# Sheet1.net
KiCad netlist of a schematic drawn in Altium Designer
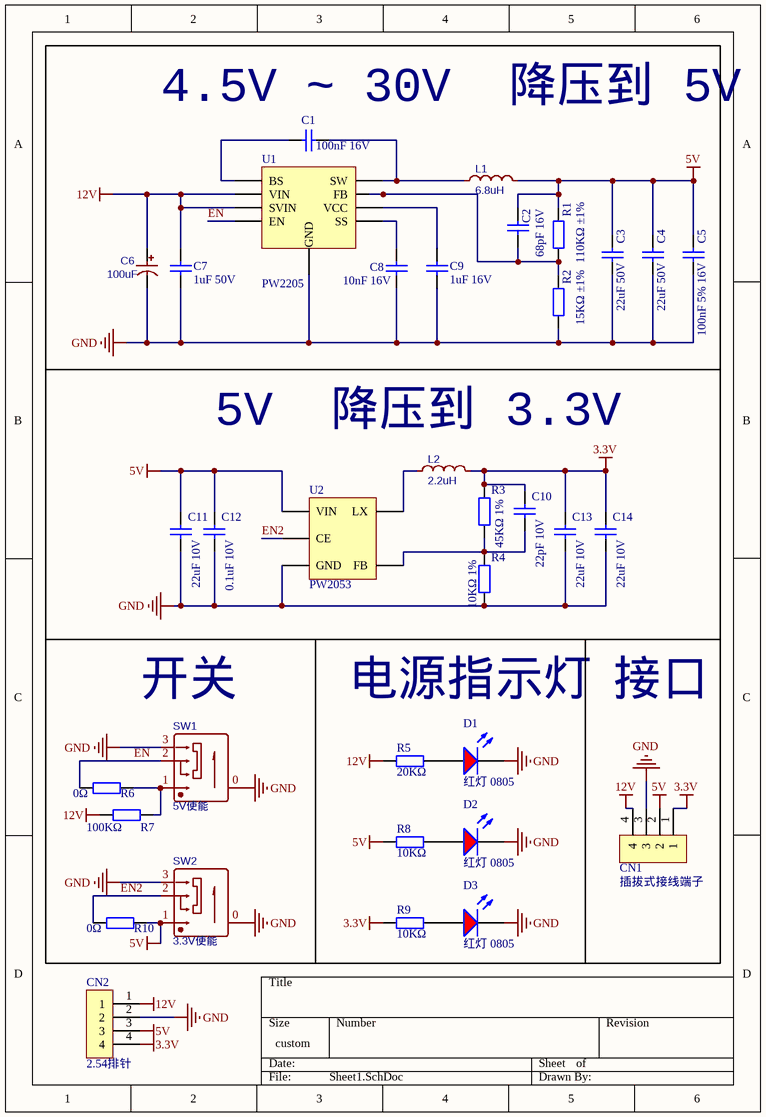
[diagram p0: Sheet1.SchDoc]

(export (version "E")
  (design (tool "Eeschema 10.0.6"))
  (components
    (comp (ref "C1")
      (value "100nF 16V")
      (footprint "0805_C")
      (description "贴片电容")
      (libsource (lib "Miscellaneous Devices LC") (part "0805 100nF(104) 10% 50V"))
    )
    (comp (ref "C2")
      (value "68pF 16V")
      (footprint "0805_C")
      (description "贴片电容")
      (libsource (lib "Miscellaneous Devices LC") (part "0805 68pF (680) 5% 50V"))
    )
    (comp (ref "C3")
      (value "22uF 50V")
      (footprint "0805_C")
      (description "贴片电容")
      (libsource (lib "Miscellaneous Devices LC") (part "0805 22uF (226) 20% 25V"))
    )
    (comp (ref "C4")
      (value "22uF 50V")
      (footprint "0805_C")
      (description "贴片电容")
      (libsource (lib "Miscellaneous Devices LC") (part "0805 22uF (226) 20% 25V"))
    )
    (comp (ref "C5")
      (value "100nF 5% 16V")
      (footprint "0805_C")
      (description "贴片电容")
      (libsource (lib "Miscellaneous Devices LC") (part "0805 100nF(104) 10% 50V"))
    )
    (comp (ref "C6")
      (value "100uF")
      (footprint "电容 6.3*8")
      (fields
        (field (name "BOM_MANUFACTURER PART") "SPZ1VM101E08000R")
        (field (name "BOM_SUPPLIER PART") "C122240")
      )
      (libsource (lib "BalanceCar") (part "电容 6.3*8"))
    )
    (comp (ref "C7")
      (value "1uF 50V")
      (footprint "0805_C")
      (description "贴片电容")
      (libsource (lib "Miscellaneous Devices LC") (part "0805 1uF (105) 10% 50V"))
    )
    (comp (ref "C8")
      (value "10nF 16V")
      (footprint "0805_C")
      (description "贴片电容")
      (libsource (lib "Miscellaneous Devices LC") (part "0805 10nF (103) 10% 50V"))
    )
    (comp (ref "C9")
      (value "1uF 16V")
      (footprint "0805_C")
      (description "贴片电容")
      (libsource (lib "Miscellaneous Devices LC") (part "0805 1uF (105) 10% 50V"))
    )
    (comp (ref "C10")
      (value "22pF 10V")
      (footprint "0805_C")
      (description "贴片电容")
      (libsource (lib "Miscellaneous Devices LC") (part "0603 10pF (100) 5% 50V"))
    )
    (comp (ref "C11")
      (value "22uF 10V")
      (footprint "0805_C")
      (description "贴片电容")
      (libsource (lib "Miscellaneous Devices LC") (part "0805 22uF (226) 20% 25V"))
    )
    (comp (ref "C12")
      (value "0.1uF 10V")
      (footprint "0805_C")
      (description "贴片电容")
      (libsource (lib "Miscellaneous Devices LC") (part "0603 10pF (100) 5% 50V"))
    )
    (comp (ref "C13")
      (value "22uF 10V")
      (footprint "0805_C")
      (description "贴片电容")
      (libsource (lib "Miscellaneous Devices LC") (part "0805 22uF (226) 20% 25V"))
    )
    (comp (ref "C14")
      (value "22uF 10V")
      (footprint "0805_C")
      (description "贴片电容")
      (libsource (lib "Miscellaneous Devices LC") (part "0805 22uF (226) 20% 25V"))
    )
    (comp (ref "CN1")
      (value "插拔式接线端子")
      (footprint "插拔式接线端子-弯插")
      (libsource (lib "DCDC_Power") (part "插拔式接线端子"))
    )
    (comp (ref "CN2") (value "2.54排针") (footprint "2.54排针") (libsource (lib "DCDC_Power") (part "2.54排针")))
    (comp (ref "D1")
      (value "红灯 0805")
      (footprint "0805_LED_S1")
      (description "发光二极管")
      (libsource (lib "Miscellaneous Devices LC") (part "0805 红灯"))
    )
    (comp (ref "D2")
      (value "红灯 0805")
      (footprint "0805_LED_S1")
      (description "发光二极管")
      (libsource (lib "Miscellaneous Devices LC") (part "0805 红灯"))
    )
    (comp (ref "D3")
      (value "红灯 0805")
      (footprint "0805_LED_S1")
      (description "发光二极管")
      (libsource (lib "Miscellaneous Devices LC") (part "0805 红灯"))
    )
    (comp (ref "L1")
      (value "6.8uH")
      (footprint "电感 0650")
      (fields
        (field (name "BOM_SUPPLIER PART") "C475530")
        (field (name "BOM_MANUFACTURER PART") "FXL0650-6R8-M")
        (field (name "CONTRIBUTOR") "LCSC")
      )
      (libsource (lib "BalanceCar") (part "电感 6.8uH"))
    )
    (comp (ref "L2")
      (value "2.2uH")
      (footprint "电感 0520")
      (fields
        (field (name "BOM_SUPPLIER PART") "C475530")
        (field (name "BOM_MANUFACTURER PART") "FXL0650-6R8-M")
        (field (name "CONTRIBUTOR") "LCSC")
      )
      (libsource (lib "") (part "电感 6.8uH_1"))
    )
    (comp (ref "R1")
      (value "110KΩ ±1%")
      (footprint "0805_R")
      (description "贴片电阻")
      (libsource (lib "Miscellaneous Devices LC") (part "0805 110KΩ (1103) 1%"))
    )
    (comp (ref "R2")
      (value "15KΩ ±1%")
      (footprint "0805_R")
      (description "贴片电阻")
      (libsource (lib "Miscellaneous Devices LC") (part "0805 15KΩ (1502) 1%"))
    )
    (comp (ref "R3")
      (value "45KΩ 1%")
      (footprint "0805_R")
      (description "贴片电阻")
      (libsource (lib "Miscellaneous Devices LC") (part "0603 10KΩ (1002) 1%"))
    )
    (comp (ref "R4")
      (value "10KΩ 1%")
      (footprint "0805_R")
      (description "贴片电阻")
      (libsource (lib "Miscellaneous Devices LC") (part "0603 10KΩ (1002) 1%"))
    )
    (comp (ref "R5")
      (value "20KΩ")
      (footprint "0805_R")
      (description "贴片电阻")
      (libsource (lib "Miscellaneous Devices LC") (part "0805 4.7KΩ (4701) 1%"))
    )
    (comp (ref "R6")
      (value "0Ω")
      (footprint "0805_R")
      (description "贴片电阻")
      (libsource (lib "Miscellaneous Devices LC") (part "0805 0Ω (0R0) 1%"))
    )
    (comp (ref "R7")
      (value "100KΩ")
      (footprint "0805_R")
      (description "贴片电阻")
      (libsource (lib "Miscellaneous Devices LC") (part "0805 100KΩ (1003) 1%"))
    )
    (comp (ref "R8")
      (value "10KΩ")
      (footprint "0805_R")
      (description "贴片电阻")
      (libsource (lib "Miscellaneous Devices LC") (part "0805 1KΩ (1001) 1%"))
    )
    (comp (ref "R9")
      (value "10KΩ")
      (footprint "0805_R")
      (description "贴片电阻")
      (libsource (lib "Miscellaneous Devices LC") (part "0805 1KΩ (1001) 1%"))
    )
    (comp (ref "R10")
      (value "0Ω")
      (footprint "0805_R")
      (description "贴片电阻")
      (libsource (lib "Miscellaneous Devices LC") (part "0805 0Ω (0R0) 1%"))
    )
    (comp (ref "SW1")
      (value "5V使能")
      (footprint "拨动开关(侧)")
      (fields
        (field (name "BOM_SUPPLIER PART") "C319020")
        (field (name "BOM_MANUFACTURER PART") "SK-3296S-01-L1")
        (field (name "CONTRIBUTOR") "LCSC")
      )
      (libsource (lib "DCDC_Power") (part "拨动开关(侧)"))
    )
    (comp (ref "SW2")
      (value "3.3V使能")
      (footprint "拨动开关(侧)")
      (fields
        (field (name "BOM_SUPPLIER PART") "C319020")
        (field (name "BOM_MANUFACTURER PART") "SK-3296S-01-L1")
        (field (name "CONTRIBUTOR") "LCSC")
      )
      (libsource (lib "DCDC_Power") (part "拨动开关(侧)"))
    )
    (comp (ref "U1")
      (value "PW2205")
      (footprint "PW2205 - SOP8")
      (libsource (lib "BalanceCar") (part "PW2205"))
    )
    (comp (ref "U2")
      (value "PW2053")
      (footprint "PW2053 - SOT23-6")
      (libsource (lib "BalanceCar") (part "PW2053"))
    )
  )
  (nets
    (net (code "1") (name "/EN") (class "Default")
      (node (ref "R6") (pin "1") (pinfunction "1_1") (pintype "passive"))
      (node (ref "SW1") (pin "2") (pinfunction "2_2") (pintype "passive"))
      (node (ref "U1") (pin "EN") (pinfunction "EN_EN") (pintype "passive"))
    )
    (net (code "2") (name "/EN2") (class "Default")
      (node (ref "R10") (pin "1") (pinfunction "1_1") (pintype "passive"))
      (node (ref "SW2") (pin "2") (pinfunction "2_2") (pintype "passive"))
      (node (ref "U2") (pin "CE") (pinfunction "CE_CE") (pintype "passive"))
    )
    (net (code "3") (name "3.3V") (class "Default")
      (node (ref "C10") (pin "2") (pinfunction "2_2") (pintype "passive"))
      (node (ref "C13") (pin "2") (pinfunction "2_2") (pintype "passive"))
      (node (ref "C14") (pin "2") (pinfunction "2_2") (pintype "passive"))
      (node (ref "CN1") (pin "1") (pinfunction "1_1") (pintype "passive"))
      (node (ref "CN2") (pin "4") (pinfunction "4_4") (pintype "passive"))
      (node (ref "L2") (pin "2") (pinfunction "2_2") (pintype "passive"))
      (node (ref "R3") (pin "2") (pinfunction "2_2") (pintype "passive"))
      (node (ref "R9") (pin "1") (pinfunction "1_1") (pintype "passive"))
    )
    (net (code "4") (name "5V") (class "Default")
      (node (ref "C11") (pin "2") (pinfunction "2_2") (pintype "passive"))
      (node (ref "C12") (pin "2") (pinfunction "2_2") (pintype "passive"))
      (node (ref "C2") (pin "2") (pinfunction "2_2") (pintype "passive"))
      (node (ref "C3") (pin "2") (pinfunction "2_2") (pintype "passive"))
      (node (ref "C4") (pin "2") (pinfunction "2_2") (pintype "passive"))
      (node (ref "C5") (pin "2") (pinfunction "2_2") (pintype "passive"))
      (node (ref "CN1") (pin "2") (pinfunction "2_2") (pintype "passive"))
      (node (ref "CN2") (pin "3") (pinfunction "3_3") (pintype "passive"))
      (node (ref "L1") (pin "2") (pinfunction "2_2") (pintype "output"))
      (node (ref "R1") (pin "2") (pinfunction "2_2") (pintype "passive"))
      (node (ref "R10") (pin "2") (pinfunction "2_2") (pintype "passive"))
      (node (ref "R8") (pin "1") (pinfunction "1_1") (pintype "passive"))
      (node (ref "SW2") (pin "1") (pinfunction "1_1") (pintype "passive"))
      (node (ref "U2") (pin "VIN") (pinfunction "VIN_VIN") (pintype "passive"))
    )
    (net (code "5") (name "12V") (class "Default")
      (node (ref "C6") (pin "1") (pinfunction "1_1") (pintype "passive"))
      (node (ref "C7") (pin "2") (pinfunction "2_2") (pintype "passive"))
      (node (ref "CN1") (pin "4") (pinfunction "4_4") (pintype "passive"))
      (node (ref "CN2") (pin "1") (pinfunction "1_1") (pintype "passive"))
      (node (ref "R5") (pin "1") (pinfunction "1_1") (pintype "passive"))
      (node (ref "R7") (pin "1") (pinfunction "1_1") (pintype "passive"))
      (node (ref "U1") (pin "SVIN") (pinfunction "SVIN_SVIN") (pintype "passive"))
      (node (ref "U1") (pin "VIN") (pinfunction "VIN_VIN") (pintype "passive"))
    )
    (net (code "6") (name "GND") (class "Default")
      (node (ref "C11") (pin "1") (pinfunction "1_1") (pintype "passive"))
      (node (ref "C12") (pin "1") (pinfunction "1_1") (pintype "passive"))
      (node (ref "C13") (pin "1") (pinfunction "1_1") (pintype "passive"))
      (node (ref "C14") (pin "1") (pinfunction "1_1") (pintype "passive"))
      (node (ref "C3") (pin "1") (pinfunction "1_1") (pintype "passive"))
      (node (ref "C4") (pin "1") (pinfunction "1_1") (pintype "passive"))
      (node (ref "C5") (pin "1") (pinfunction "1_1") (pintype "passive"))
      (node (ref "C6") (pin "2") (pinfunction "2_2") (pintype "passive"))
      (node (ref "C7") (pin "1") (pinfunction "1_1") (pintype "passive"))
      (node (ref "C8") (pin "1") (pinfunction "1_1") (pintype "passive"))
      (node (ref "C9") (pin "1") (pinfunction "1_1") (pintype "passive"))
      (node (ref "CN1") (pin "3") (pinfunction "3_3") (pintype "passive"))
      (node (ref "CN2") (pin "2") (pinfunction "2_2") (pintype "passive"))
      (node (ref "D1") (pin "K") (pinfunction "K_K") (pintype "passive"))
      (node (ref "D2") (pin "K") (pinfunction "K_K") (pintype "passive"))
      (node (ref "D3") (pin "K") (pinfunction "K_K") (pintype "passive"))
      (node (ref "R2") (pin "1") (pinfunction "1_1") (pintype "passive"))
      (node (ref "R4") (pin "1") (pinfunction "1_1") (pintype "passive"))
      (node (ref "SW1") (pin "0") (pinfunction "0_0") (pintype "passive"))
      (node (ref "SW1") (pin "3") (pinfunction "3_3") (pintype "passive"))
      (node (ref "SW2") (pin "0") (pinfunction "0_0") (pintype "passive"))
      (node (ref "SW2") (pin "3") (pinfunction "3_3") (pintype "passive"))
      (node (ref "U1") (pin "GND") (pinfunction "GND_GND") (pintype "passive"))
      (node (ref "U2") (pin "GND") (pinfunction "GND_GND") (pintype "passive"))
    )
    (net (code "7") (name "Net-(C1-Pad1)") (class "Default")
      (node (ref "C1") (pin "1") (pinfunction "1_1") (pintype "passive"))
      (node (ref "U1") (pin "BS") (pinfunction "BS_BS") (pintype "passive"))
    )
    (net (code "8") (name "Net-(C1-Pad2)") (class "Default")
      (node (ref "C1") (pin "2") (pinfunction "2_2") (pintype "passive"))
      (node (ref "L1") (pin "1") (pinfunction "1_1") (pintype "passive"))
      (node (ref "U1") (pin "SW") (pinfunction "SW_SW") (pintype "passive"))
    )
    (net (code "9") (name "Net-(C2-Pad1)") (class "Default")
      (node (ref "C2") (pin "1") (pinfunction "1_1") (pintype "passive"))
      (node (ref "R1") (pin "1") (pinfunction "1_1") (pintype "passive"))
      (node (ref "R2") (pin "2") (pinfunction "2_2") (pintype "passive"))
      (node (ref "U1") (pin "FB") (pinfunction "FB_FB") (pintype "passive"))
    )
    (net (code "10") (name "Net-(C8-Pad2)") (class "Default")
      (node (ref "C8") (pin "2") (pinfunction "2_2") (pintype "passive"))
      (node (ref "U1") (pin "SS") (pinfunction "SS_SS") (pintype "passive"))
    )
    (net (code "11") (name "Net-(C9-Pad2)") (class "Default")
      (node (ref "C9") (pin "2") (pinfunction "2_2") (pintype "passive"))
      (node (ref "U1") (pin "VCC") (pinfunction "VCC_VCC") (pintype "passive"))
    )
    (net (code "12") (name "Net-(C10-Pad1)") (class "Default")
      (node (ref "C10") (pin "1") (pinfunction "1_1") (pintype "passive"))
      (node (ref "R3") (pin "1") (pinfunction "1_1") (pintype "passive"))
      (node (ref "R4") (pin "2") (pinfunction "2_2") (pintype "passive"))
      (node (ref "U2") (pin "FB") (pinfunction "FB_FB") (pintype "passive"))
    )
    (net (code "13") (name "Net-(D1-PadA)") (class "Default")
      (node (ref "D1") (pin "A") (pinfunction "A_A") (pintype "passive"))
      (node (ref "R5") (pin "2") (pinfunction "2_2") (pintype "passive"))
    )
    (net (code "14") (name "Net-(D2-PadA)") (class "Default")
      (node (ref "D2") (pin "A") (pinfunction "A_A") (pintype "passive"))
      (node (ref "R8") (pin "2") (pinfunction "2_2") (pintype "passive"))
    )
    (net (code "15") (name "Net-(D3-PadA)") (class "Default")
      (node (ref "D3") (pin "A") (pinfunction "A_A") (pintype "passive"))
      (node (ref "R9") (pin "2") (pinfunction "2_2") (pintype "passive"))
    )
    (net (code "16") (name "Net-(L2-Pad1)") (class "Default")
      (node (ref "L2") (pin "1") (pinfunction "1_1") (pintype "passive"))
      (node (ref "U2") (pin "LX") (pinfunction "LX_LX") (pintype "passive"))
    )
    (net (code "17") (name "Net-(R6-Pad2)") (class "Default")
      (node (ref "R6") (pin "2") (pinfunction "2_2") (pintype "passive"))
      (node (ref "R7") (pin "2") (pinfunction "2_2") (pintype "passive"))
      (node (ref "SW1") (pin "1") (pinfunction "1_1") (pintype "passive"))
    )
  )
)
